# Covox_stereo.net
KiCad netlist of a schematic drawn in EAGLE
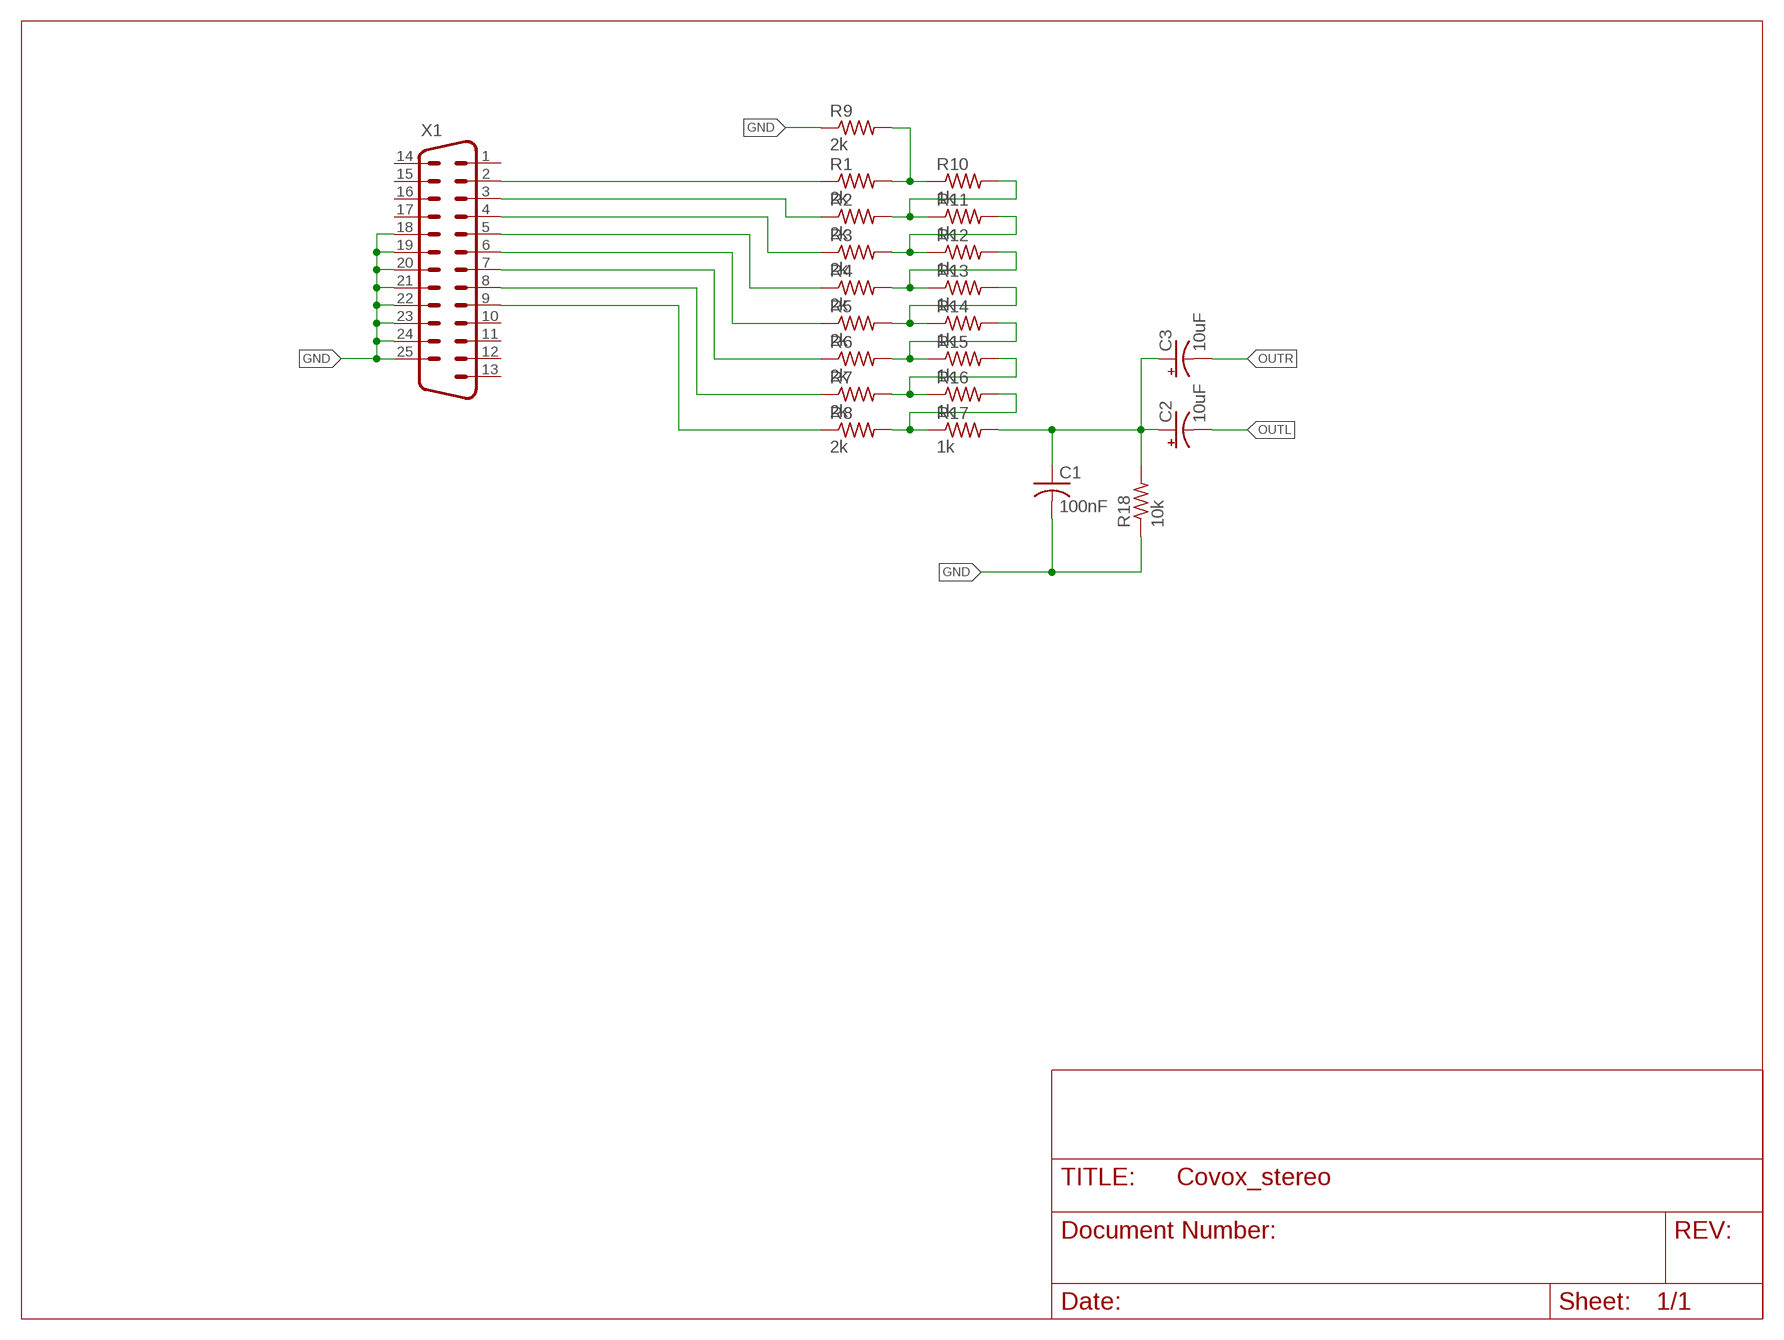
[diagram p0: schematic, sheet 1]

(export (version "E")
  (design (tool "Eeschema 10.0.6"))
  (components
    (comp (ref "C1")
      (value "100nF")
      (footprint "eagle-import:C0805K")
      (libsource (lib "eagle-import") (part "C-USC0805K"))
    )
    (comp (ref "C2")
      (value "10uF")
      (footprint "eagle-import:153CLV-0405")
      (libsource (lib "eagle-import") (part "CPOL-US153CLV-0405"))
    )
    (comp (ref "C3")
      (value "10uF")
      (footprint "eagle-import:153CLV-0405")
      (libsource (lib "eagle-import") (part "CPOL-US153CLV-0405"))
    )
    (comp (ref "R1")
      (value "2k")
      (footprint "eagle-import:M0805")
      (libsource (lib "eagle-import") (part "R-US_M0805"))
    )
    (comp (ref "R2")
      (value "2k")
      (footprint "eagle-import:M0805")
      (libsource (lib "eagle-import") (part "R-US_M0805"))
    )
    (comp (ref "R3")
      (value "2k")
      (footprint "eagle-import:M0805")
      (libsource (lib "eagle-import") (part "R-US_M0805"))
    )
    (comp (ref "R4")
      (value "2k")
      (footprint "eagle-import:M0805")
      (libsource (lib "eagle-import") (part "R-US_M0805"))
    )
    (comp (ref "R5")
      (value "2k")
      (footprint "eagle-import:M0805")
      (libsource (lib "eagle-import") (part "R-US_M0805"))
    )
    (comp (ref "R6")
      (value "2k")
      (footprint "eagle-import:M0805")
      (libsource (lib "eagle-import") (part "R-US_M0805"))
    )
    (comp (ref "R7")
      (value "2k")
      (footprint "eagle-import:M0805")
      (libsource (lib "eagle-import") (part "R-US_M0805"))
    )
    (comp (ref "R8")
      (value "2k")
      (footprint "eagle-import:M0805")
      (libsource (lib "eagle-import") (part "R-US_M0805"))
    )
    (comp (ref "R9")
      (value "2k")
      (footprint "eagle-import:M0805")
      (libsource (lib "eagle-import") (part "R-US_M0805"))
    )
    (comp (ref "R10")
      (value "1k")
      (footprint "eagle-import:M0805")
      (libsource (lib "eagle-import") (part "R-US_M0805"))
    )
    (comp (ref "R11")
      (value "1k")
      (footprint "eagle-import:M0805")
      (libsource (lib "eagle-import") (part "R-US_M0805"))
    )
    (comp (ref "R12")
      (value "1k")
      (footprint "eagle-import:M0805")
      (libsource (lib "eagle-import") (part "R-US_M0805"))
    )
    (comp (ref "R13")
      (value "1k")
      (footprint "eagle-import:M0805")
      (libsource (lib "eagle-import") (part "R-US_M0805"))
    )
    (comp (ref "R14")
      (value "1k")
      (footprint "eagle-import:M0805")
      (libsource (lib "eagle-import") (part "R-US_M0805"))
    )
    (comp (ref "R15")
      (value "1k")
      (footprint "eagle-import:M0805")
      (libsource (lib "eagle-import") (part "R-US_M0805"))
    )
    (comp (ref "R16")
      (value "1k")
      (footprint "eagle-import:M0805")
      (libsource (lib "eagle-import") (part "R-US_M0805"))
    )
    (comp (ref "R17")
      (value "1k")
      (footprint "eagle-import:M0805")
      (libsource (lib "eagle-import") (part "R-US_M0805"))
    )
    (comp (ref "R18")
      (value "10k")
      (footprint "eagle-import:M0805")
      (libsource (lib "eagle-import") (part "R-US_M0805"))
    )
    (comp (ref "X1")
      (value "DB25D")
      (footprint "eagle-import:M25D")
      (libsource (lib "eagle-import") (part "DB25D"))
    )
  )
  (nets
    (net (code "1") (name "GND") (class "Default")
      (node (ref "C1") (pin "2") (pinfunction "2_2") (pintype "passive"))
      (node (ref "R18") (pin "1") (pinfunction "1_1") (pintype "passive"))
      (node (ref "R9") (pin "1") (pinfunction "1_1") (pintype "passive"))
      (node (ref "X1") (pin "18") (pinfunction "18_18") (pintype "passive"))
      (node (ref "X1") (pin "19") (pinfunction "19_19") (pintype "passive"))
      (node (ref "X1") (pin "20") (pinfunction "20_20") (pintype "passive"))
      (node (ref "X1") (pin "21") (pinfunction "21_21") (pintype "passive"))
      (node (ref "X1") (pin "22") (pinfunction "22_22") (pintype "passive"))
      (node (ref "X1") (pin "23") (pinfunction "23_23") (pintype "passive"))
      (node (ref "X1") (pin "24") (pinfunction "24_24") (pintype "passive"))
      (node (ref "X1") (pin "25") (pinfunction "25_25") (pintype "passive"))
    )
    (net (code "2") (name "Net-(C1-Pad1)") (class "Default")
      (node (ref "C1") (pin "1") (pinfunction "1_1") (pintype "passive"))
      (node (ref "C2") (pin "+") (pinfunction "+_+") (pintype "passive"))
      (node (ref "C3") (pin "+") (pinfunction "+_+") (pintype "passive"))
      (node (ref "R17") (pin "2") (pinfunction "2_2") (pintype "passive"))
      (node (ref "R18") (pin "2") (pinfunction "2_2") (pintype "passive"))
    )
    (net (code "3") (name "Net-(R1-Pad1)") (class "Default")
      (node (ref "R1") (pin "1") (pinfunction "1_1") (pintype "passive"))
      (node (ref "X1") (pin "2") (pinfunction "2_2") (pintype "passive"))
    )
    (net (code "4") (name "Net-(R1-Pad2)") (class "Default")
      (node (ref "R1") (pin "2") (pinfunction "2_2") (pintype "passive"))
      (node (ref "R10") (pin "1") (pinfunction "1_1") (pintype "passive"))
      (node (ref "R9") (pin "2") (pinfunction "2_2") (pintype "passive"))
    )
    (net (code "5") (name "Net-(R2-Pad1)") (class "Default")
      (node (ref "R2") (pin "1") (pinfunction "1_1") (pintype "passive"))
      (node (ref "X1") (pin "3") (pinfunction "3_3") (pintype "passive"))
    )
    (net (code "6") (name "Net-(R3-Pad1)") (class "Default")
      (node (ref "R3") (pin "1") (pinfunction "1_1") (pintype "passive"))
      (node (ref "X1") (pin "4") (pinfunction "4_4") (pintype "passive"))
    )
    (net (code "7") (name "Net-(R4-Pad1)") (class "Default")
      (node (ref "R4") (pin "1") (pinfunction "1_1") (pintype "passive"))
      (node (ref "X1") (pin "5") (pinfunction "5_5") (pintype "passive"))
    )
    (net (code "8") (name "Net-(R5-Pad1)") (class "Default")
      (node (ref "R5") (pin "1") (pinfunction "1_1") (pintype "passive"))
      (node (ref "X1") (pin "6") (pinfunction "6_6") (pintype "passive"))
    )
    (net (code "9") (name "Net-(R6-Pad1)") (class "Default")
      (node (ref "R6") (pin "1") (pinfunction "1_1") (pintype "passive"))
      (node (ref "X1") (pin "7") (pinfunction "7_7") (pintype "passive"))
    )
    (net (code "10") (name "Net-(R7-Pad1)") (class "Default")
      (node (ref "R7") (pin "1") (pinfunction "1_1") (pintype "passive"))
      (node (ref "X1") (pin "8") (pinfunction "8_8") (pintype "passive"))
    )
    (net (code "11") (name "Net-(R8-Pad1)") (class "Default")
      (node (ref "R8") (pin "1") (pinfunction "1_1") (pintype "passive"))
      (node (ref "X1") (pin "9") (pinfunction "9_9") (pintype "passive"))
    )
    (net (code "12") (name "Net-(R10-Pad2)") (class "Default")
      (node (ref "R10") (pin "2") (pinfunction "2_2") (pintype "passive"))
      (node (ref "R11") (pin "1") (pinfunction "1_1") (pintype "passive"))
      (node (ref "R2") (pin "2") (pinfunction "2_2") (pintype "passive"))
    )
    (net (code "13") (name "Net-(R11-Pad2)") (class "Default")
      (node (ref "R11") (pin "2") (pinfunction "2_2") (pintype "passive"))
      (node (ref "R12") (pin "1") (pinfunction "1_1") (pintype "passive"))
      (node (ref "R3") (pin "2") (pinfunction "2_2") (pintype "passive"))
    )
    (net (code "14") (name "Net-(R12-Pad2)") (class "Default")
      (node (ref "R12") (pin "2") (pinfunction "2_2") (pintype "passive"))
      (node (ref "R13") (pin "1") (pinfunction "1_1") (pintype "passive"))
      (node (ref "R4") (pin "2") (pinfunction "2_2") (pintype "passive"))
    )
    (net (code "15") (name "Net-(R13-Pad2)") (class "Default")
      (node (ref "R13") (pin "2") (pinfunction "2_2") (pintype "passive"))
      (node (ref "R14") (pin "1") (pinfunction "1_1") (pintype "passive"))
      (node (ref "R5") (pin "2") (pinfunction "2_2") (pintype "passive"))
    )
    (net (code "16") (name "Net-(R14-Pad2)") (class "Default")
      (node (ref "R14") (pin "2") (pinfunction "2_2") (pintype "passive"))
      (node (ref "R15") (pin "1") (pinfunction "1_1") (pintype "passive"))
      (node (ref "R6") (pin "2") (pinfunction "2_2") (pintype "passive"))
    )
    (net (code "17") (name "Net-(R15-Pad2)") (class "Default")
      (node (ref "R15") (pin "2") (pinfunction "2_2") (pintype "passive"))
      (node (ref "R16") (pin "1") (pinfunction "1_1") (pintype "passive"))
      (node (ref "R7") (pin "2") (pinfunction "2_2") (pintype "passive"))
    )
    (net (code "18") (name "Net-(R16-Pad2)") (class "Default")
      (node (ref "R16") (pin "2") (pinfunction "2_2") (pintype "passive"))
      (node (ref "R17") (pin "1") (pinfunction "1_1") (pintype "passive"))
      (node (ref "R8") (pin "2") (pinfunction "2_2") (pintype "passive"))
    )
    (net (code "19") (name "OUTL") (class "Default")
      (node (ref "C2") (pin "-") (pinfunction "-_-") (pintype "passive"))
    )
    (net (code "20") (name "OUTR") (class "Default")
      (node (ref "C3") (pin "-") (pinfunction "-_-") (pintype "passive"))
    )
    (net (code "21") (name "unconnected-(X1-Pad1)") (class "Default")
      (node (ref "X1") (pin "1") (pinfunction "1_1") (pintype "passive"))
    )
    (net (code "22") (name "unconnected-(X1-Pad10)") (class "Default")
      (node (ref "X1") (pin "10") (pinfunction "10_10") (pintype "passive"))
    )
    (net (code "23") (name "unconnected-(X1-Pad11)") (class "Default")
      (node (ref "X1") (pin "11") (pinfunction "11_11") (pintype "passive"))
    )
    (net (code "24") (name "unconnected-(X1-Pad12)") (class "Default")
      (node (ref "X1") (pin "12") (pinfunction "12_12") (pintype "passive"))
    )
    (net (code "25") (name "unconnected-(X1-Pad13)") (class "Default")
      (node (ref "X1") (pin "13") (pinfunction "13_13") (pintype "passive"))
    )
    (net (code "26") (name "unconnected-(X1-Pad14)") (class "Default")
      (node (ref "X1") (pin "14") (pinfunction "14_14") (pintype "passive"))
    )
    (net (code "27") (name "unconnected-(X1-Pad15)") (class "Default")
      (node (ref "X1") (pin "15") (pinfunction "15_15") (pintype "passive"))
    )
    (net (code "28") (name "unconnected-(X1-Pad16)") (class "Default")
      (node (ref "X1") (pin "16") (pinfunction "16_16") (pintype "passive"))
    )
    (net (code "29") (name "unconnected-(X1-Pad17)") (class "Default")
      (node (ref "X1") (pin "17") (pinfunction "17_17") (pintype "passive"))
    )
  )
)
